# design1.net
KiCad netlist of a schematic drawn in EAGLE
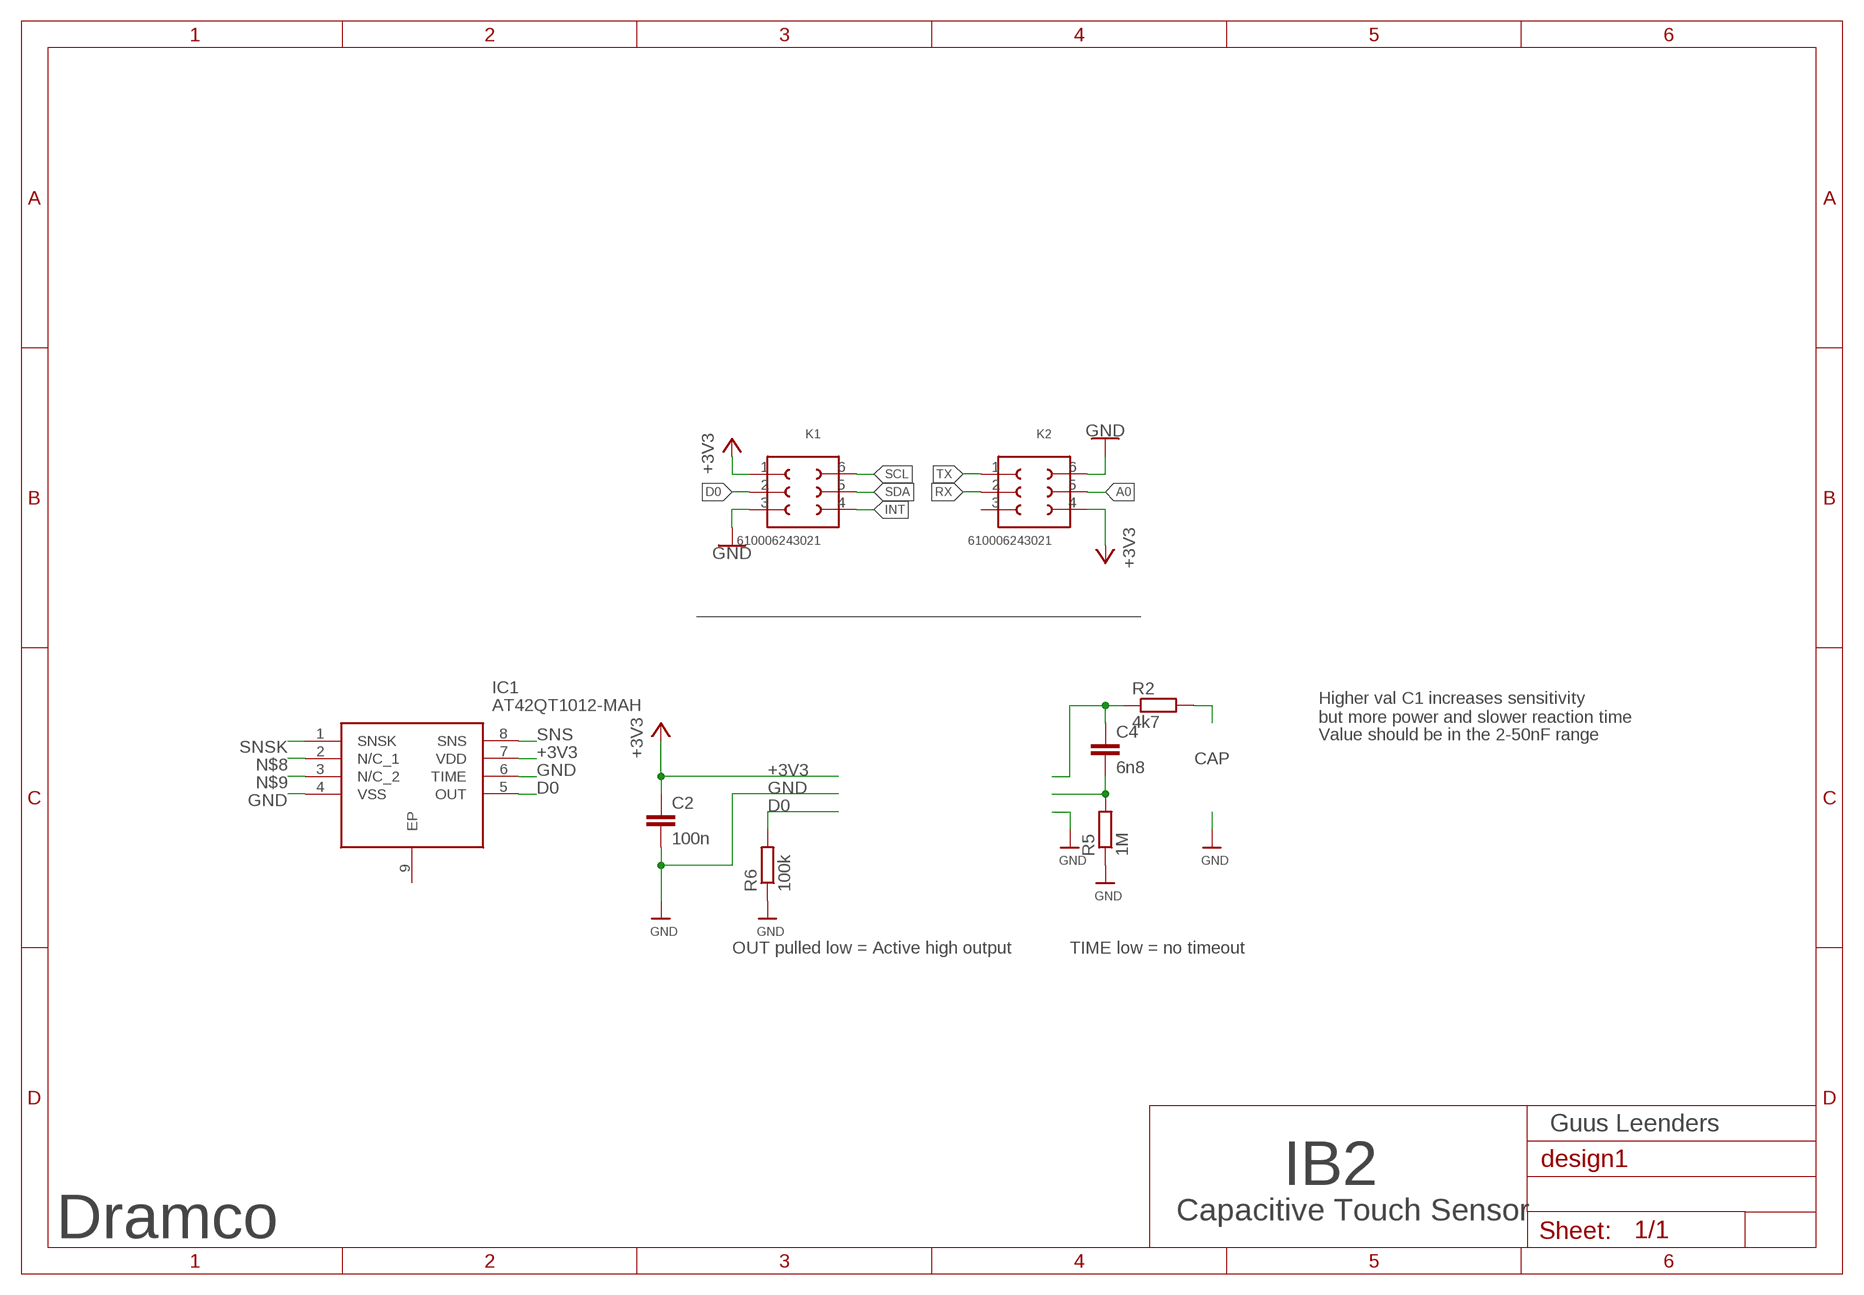
[diagram p0: schematic, sheet 1]

(export (version "E")
  (design (tool "Eeschema 10.0.6"))
  (components
    (comp (ref "C2")
      (value "100n")
      (footprint "eagle-import:C0603")
      (libsource (lib "eagle-import") (part "C-EUC0603"))
    )
    (comp (ref "C4")
      (value "6n8")
      (footprint "eagle-import:C0603")
      (libsource (lib "eagle-import") (part "C-EUC0603"))
    )
    (comp (ref "IC1")
      (value "AT42QT1012-MAH")
      (footprint "eagle-import:SON50P200X200X60-9N")
      (fields (field (name "MOUSER_PART_NUMBER") "556-AT42QT1012-MAH"))
      (libsource (lib "eagle-import") (part "AT42QT1012-MAH"))
    )
    (comp (ref "K1")
      (value "610006243021")
      (footprint "eagle-import:610006243021")
      (libsource (lib "eagle-import") (part "610006243021"))
    )
    (comp (ref "K2")
      (value "610006243021")
      (footprint "eagle-import:610006243021")
      (libsource (lib "eagle-import") (part "610006243021"))
    )
    (comp (ref "R2")
      (value "4k7")
      (footprint "eagle-import:R0603")
      (libsource (lib "eagle-import") (part "R-EU_R0603"))
    )
    (comp (ref "R5")
      (value "1M")
      (footprint "eagle-import:R0603")
      (libsource (lib "eagle-import") (part "R-EU_R0603"))
    )
    (comp (ref "R6")
      (value "100k")
      (footprint "eagle-import:R0603")
      (libsource (lib "eagle-import") (part "R-EU_R0603"))
    )
  )
  (nets
    (net (code "1") (name "+3V3") (class "Default")
      (node (ref "C2") (pin "1") (pinfunction "1_1") (pintype "passive"))
      (node (ref "IC1") (pin "7") (pinfunction "VDD_7") (pintype "bidirectional"))
      (node (ref "K1") (pin "1") (pinfunction "1_1") (pintype "passive"))
      (node (ref "K2") (pin "4") (pinfunction "4_4") (pintype "passive"))
    )
    (net (code "2") (name "/N$8") (class "Default")
      (node (ref "IC1") (pin "2") (pinfunction "N/C_1_2") (pintype "bidirectional"))
    )
    (net (code "3") (name "/N$9") (class "Default")
      (node (ref "IC1") (pin "3") (pinfunction "N/C_2_3") (pintype "bidirectional"))
    )
    (net (code "4") (name "/SNS") (class "Default")
      (node (ref "C4") (pin "2") (pinfunction "2_2") (pintype "passive"))
      (node (ref "IC1") (pin "8") (pinfunction "SNS_8") (pintype "bidirectional"))
      (node (ref "R5") (pin "2") (pinfunction "2_2") (pintype "passive"))
    )
    (net (code "5") (name "/SNSK") (class "Default")
      (node (ref "C4") (pin "1") (pinfunction "1_1") (pintype "passive"))
      (node (ref "IC1") (pin "1") (pinfunction "SNSK_1") (pintype "bidirectional"))
      (node (ref "R2") (pin "1") (pinfunction "1_1") (pintype "passive"))
    )
    (net (code "6") (name "A0") (class "Default")
      (node (ref "K2") (pin "5") (pinfunction "5_5") (pintype "passive"))
    )
    (net (code "7") (name "D0") (class "Default")
      (node (ref "IC1") (pin "5") (pinfunction "OUT_5") (pintype "bidirectional"))
      (node (ref "K1") (pin "2") (pinfunction "2_2") (pintype "passive"))
      (node (ref "R6") (pin "2") (pinfunction "2_2") (pintype "passive"))
    )
    (net (code "8") (name "GND") (class "Default")
      (node (ref "C2") (pin "2") (pinfunction "2_2") (pintype "passive"))
      (node (ref "IC1") (pin "4") (pinfunction "VSS_4") (pintype "bidirectional"))
      (node (ref "IC1") (pin "6") (pinfunction "TIME_6") (pintype "bidirectional"))
      (node (ref "K1") (pin "3") (pinfunction "3_3") (pintype "passive"))
      (node (ref "K2") (pin "6") (pinfunction "6_6") (pintype "passive"))
      (node (ref "R5") (pin "1") (pinfunction "1_1") (pintype "passive"))
      (node (ref "R6") (pin "1") (pinfunction "1_1") (pintype "passive"))
    )
    (net (code "9") (name "INT") (class "Default")
      (node (ref "K1") (pin "4") (pinfunction "4_4") (pintype "passive"))
    )
    (net (code "10") (name "RX") (class "Default")
      (node (ref "K2") (pin "2") (pinfunction "2_2") (pintype "passive"))
    )
    (net (code "11") (name "SCL") (class "Default")
      (node (ref "K1") (pin "6") (pinfunction "6_6") (pintype "passive"))
    )
    (net (code "12") (name "SDA") (class "Default")
      (node (ref "K1") (pin "5") (pinfunction "5_5") (pintype "passive"))
    )
    (net (code "13") (name "TX") (class "Default")
      (node (ref "K2") (pin "1") (pinfunction "1_1") (pintype "passive"))
    )
    (net (code "14") (name "unconnected-(IC1-EP-Pad9)") (class "Default")
      (node (ref "IC1") (pin "9") (pinfunction "EP_9") (pintype "bidirectional"))
    )
    (net (code "15") (name "unconnected-(K2-Pad3)") (class "Default")
      (node (ref "K2") (pin "3") (pinfunction "3_3") (pintype "passive"))
    )
    (net (code "16") (name "unconnected-(R2-Pad2)") (class "Default")
      (node (ref "R2") (pin "2") (pinfunction "2_2") (pintype "passive"))
    )
  )
)
